# Step_Moter_Control.net
KiCad netlist of a schematic drawn in Altium Designer
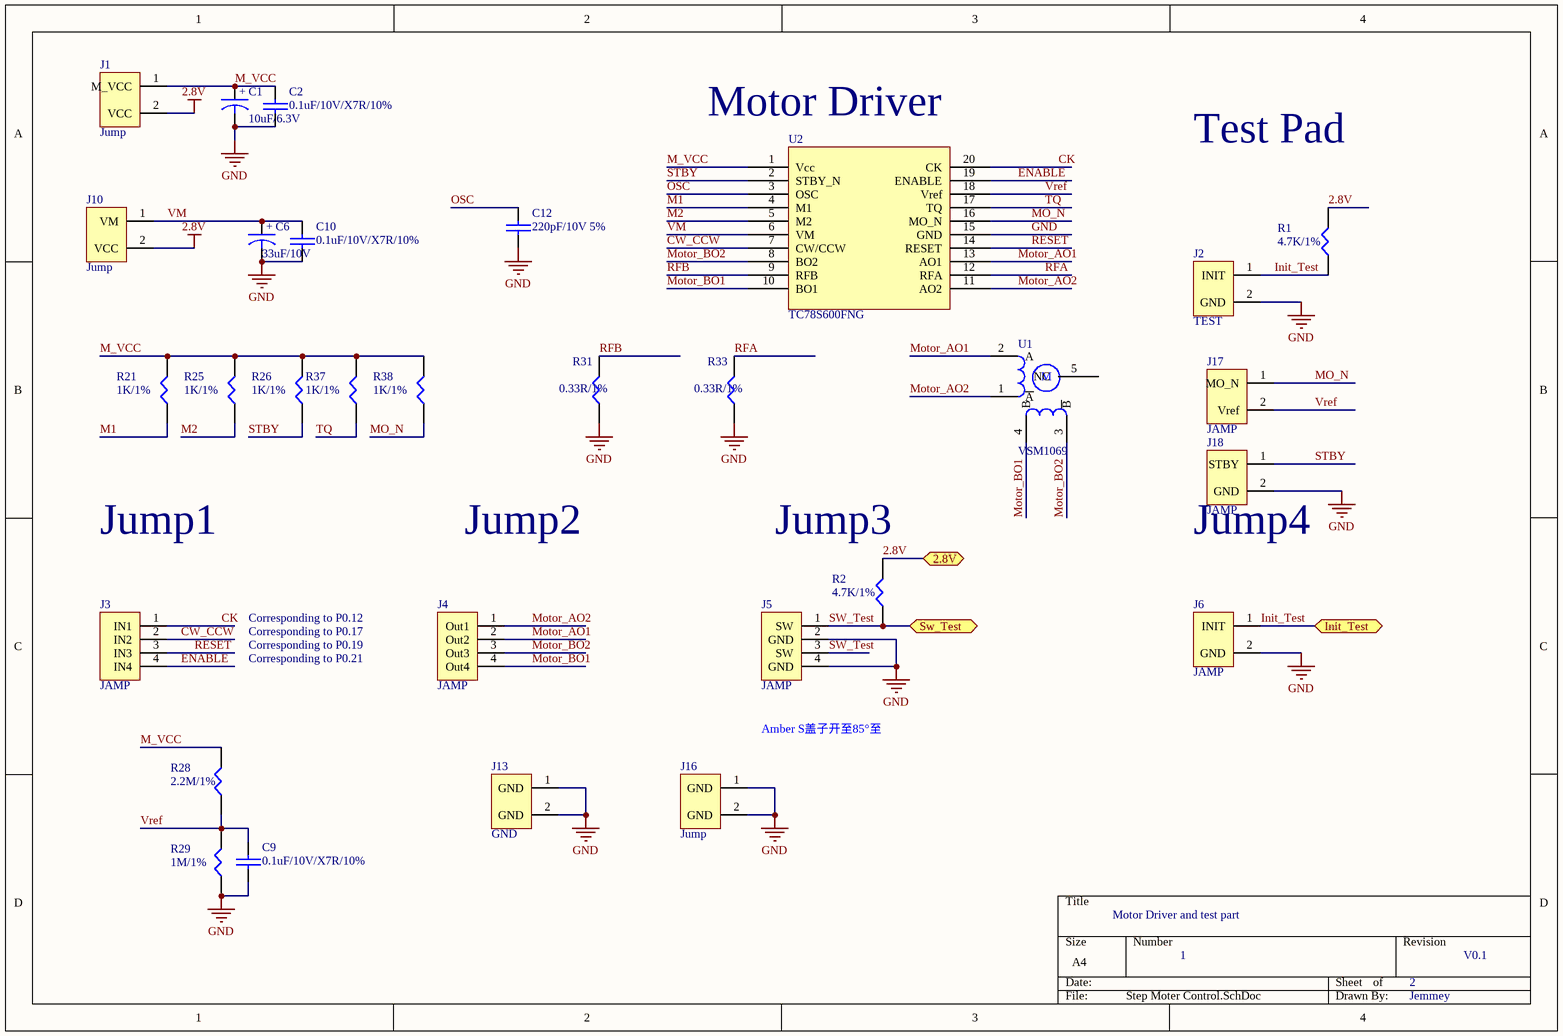
[diagram p0: Step Moter Control.SchDoc]

(export (version "E")
  (design (tool "Eeschema 10.0.6"))
  (components
    (comp (ref "C1")
      (value "10uF/6.3V")
      (footprint "3216")
      (description "厂家：ROHM，型号：")
      (libsource (lib "MoJi LIB") (part "Capacitor"))
    )
    (comp (ref "C2")
      (value "0.1uF/10V/X7R/10%")
      (footprint "0402C")
      (description "厂家：Murata，型号：GRM155R71A104KA01D")
      (libsource (lib "*") (part "CAP"))
    )
    (comp (ref "C6")
      (value "33uF/10V")
      (footprint "3216")
      (description "厂家：ROHM，型号：")
      (libsource (lib "MoJi LIB") (part "Capacitor"))
    )
    (comp (ref "C9")
      (value "0.1uF/10V/X7R/10%")
      (footprint "0402C")
      (description "厂家：Murata，型号：GRM155R71A104KA01D")
      (libsource (lib "*") (part "CAP"))
    )
    (comp (ref "C10")
      (value "0.1uF/10V/X7R/10%")
      (footprint "0402C")
      (description "厂家：Murata，型号：GRM155R71A104KA01D")
      (libsource (lib "*") (part "CAP"))
    )
    (comp (ref "C12")
      (value "220pF/10V 5%")
      (footprint "0402C")
      (description "厂家：Murata，型号：GRM155R71A104KA01D")
      (libsource (lib "*") (part "CAP"))
    )
    (comp (ref "J1")
      (value "Jump")
      (footprint "Debug- 1.27*2")
      (description "厂家：暂定，型号：暂定")
      (libsource (lib "") (part "JAMP_2"))
    )
    (comp (ref "J2")
      (value "TEST")
      (footprint "Debug- 1.27*2")
      (description "厂家：暂定，型号：暂定")
      (libsource (lib "Step Moter Control") (part "TEST"))
    )
    (comp (ref "J3")
      (value "JAMP")
      (footprint "Debug- 1.27*4")
      (description "厂家：暂定，型号：暂定")
      (libsource (lib "Step Moter Control") (part "JAMP"))
    )
    (comp (ref "J4")
      (value "JAMP")
      (footprint "Debug- 1.27*4")
      (description "厂家：暂定，型号：暂定")
      (libsource (lib "") (part "JAMP_1"))
    )
    (comp (ref "J5")
      (value "JAMP")
      (footprint "Debug- 1.27*4")
      (description "厂家：暂定，型号：暂定")
      (libsource (lib "") (part "JAMP_3"))
    )
    (comp (ref "J6")
      (value "JAMP")
      (footprint "Debug- 1.27*2")
      (description "厂家：暂定，型号：暂定")
      (libsource (lib "") (part "JAMP_2"))
    )
    (comp (ref "J10")
      (value "Jump")
      (footprint "Debug- 1.27*2")
      (description "厂家：暂定，型号：暂定")
      (libsource (lib "") (part "JAMP_2"))
    )
    (comp (ref "J13")
      (value "GND")
      (footprint "Debug- 1.27*2")
      (description "厂家：暂定，型号：暂定")
      (libsource (lib "") (part "JAMP_2"))
    )
    (comp (ref "J16")
      (value "Jump")
      (footprint "Debug- 1.27*2")
      (description "厂家：暂定，型号：暂定")
      (libsource (lib "") (part "JAMP_2"))
    )
    (comp (ref "J17")
      (value "JAMP")
      (footprint "Debug- 1.27*2")
      (description "厂家：暂定，型号：暂定")
      (libsource (lib "") (part "JAMP_2"))
    )
    (comp (ref "J18")
      (value "JAMP")
      (footprint "Debug- 1.27*2")
      (description "厂家：暂定，型号：暂定")
      (libsource (lib "") (part "JAMP_2"))
    )
    (comp (ref "R1")
      (value "4.7K/1%")
      (footprint "0402R")
      (description "厂家：Yageo，型号：RC0402FR-074K7L")
      (libsource (lib "*") (part "RES1"))
    )
    (comp (ref "R2")
      (value "4.7K/1%")
      (footprint "0402R")
      (description "厂家：Yageo，型号：RC0402FR-074K7L")
      (libsource (lib "*") (part "RES1"))
    )
    (comp (ref "R21")
      (value "1K/1%")
      (footprint "0402R")
      (description "厂家：Yageo，型号：RC0402FR-074K7L")
      (libsource (lib "*") (part "RES1"))
    )
    (comp (ref "R25")
      (value "1K/1%")
      (footprint "0402R")
      (description "厂家：Yageo，型号：RC0402FR-074K7L")
      (libsource (lib "*") (part "RES1"))
    )
    (comp (ref "R26")
      (value "1K/1%")
      (footprint "0402R")
      (description "厂家：Yageo，型号：RC0402FR-074K7L")
      (libsource (lib "*") (part "RES1"))
    )
    (comp (ref "R28")
      (value "2.2M/1%")
      (footprint "0402R")
      (description "厂家：Yageo，型号：RC0402FR-074K7L")
      (libsource (lib "*") (part "RES1"))
    )
    (comp (ref "R29")
      (value "1M/1%")
      (footprint "0402R")
      (description "厂家：Yageo，型号：RC0402FR-074K7L")
      (libsource (lib "*") (part "RES1"))
    )
    (comp (ref "R31")
      (value "0.33R/1%")
      (footprint "0603R")
      (description "厂家：Yageo，型号：RC0402FR-074K7L")
      (libsource (lib "*") (part "RES1"))
    )
    (comp (ref "R33")
      (value "0.33R/1%")
      (footprint "0603R")
      (description "厂家：Yageo，型号：RC0402FR-074K7L")
      (libsource (lib "*") (part "RES1"))
    )
    (comp (ref "R37")
      (value "1K/1%")
      (footprint "0402R")
      (description "厂家：Yageo，型号：RC0402FR-074K7L")
      (libsource (lib "*") (part "RES1"))
    )
    (comp (ref "R38")
      (value "1K/1%")
      (footprint "0402R")
      (description "厂家：Yageo，型号：RC0402FR-074K7L")
      (libsource (lib "*") (part "RES1"))
    )
    (comp (ref "U1")
      (value "VSM1069")
      (footprint "6200")
      (description "厂家：常州唯可泰，型号：VSM1069；二相步进电机")
      (libsource (lib "Step Moter Control") (part "VSM1069"))
    )
    (comp (ref "U2")
      (value "TC78S600FNG")
      (footprint "TSSOP-20")
      (libsource (lib "Step Moter Control") (part "TC78S600FNG"))
    )
  )
  (nets
    (net (code "1") (name "/CK") (class "Default")
      (node (ref "J3") (pin "1") (pinfunction "IN1_1") (pintype "passive"))
      (node (ref "U2") (pin "20") (pinfunction "CK_20") (pintype "passive"))
    )
    (net (code "2") (name "/CW_CCW") (class "Default")
      (node (ref "J3") (pin "2") (pinfunction "IN2_2") (pintype "passive"))
      (node (ref "U2") (pin "7") (pinfunction "CW/CCW_7") (pintype "passive"))
    )
    (net (code "3") (name "/ENABLE") (class "Default")
      (node (ref "J3") (pin "4") (pinfunction "IN4_4") (pintype "passive"))
      (node (ref "U2") (pin "19") (pinfunction "ENABLE_19") (pintype "passive"))
    )
    (net (code "4") (name "/Init_Test") (class "Default")
      (node (ref "J2") (pin "1") (pinfunction "INIT_1") (pintype "passive"))
      (node (ref "J6") (pin "1") (pinfunction "VM_1") (pintype "passive"))
      (node (ref "R1") (pin "1") (pinfunction "1_1") (pintype "passive"))
    )
    (net (code "5") (name "/M1") (class "Default")
      (node (ref "R21") (pin "1") (pinfunction "1_1") (pintype "passive"))
      (node (ref "U2") (pin "4") (pinfunction "M1_4") (pintype "passive"))
    )
    (net (code "6") (name "/M2") (class "Default")
      (node (ref "R25") (pin "1") (pinfunction "1_1") (pintype "passive"))
      (node (ref "U2") (pin "5") (pinfunction "M2_5") (pintype "passive"))
    )
    (net (code "7") (name "/MO_N") (class "Default")
      (node (ref "J17") (pin "1") (pinfunction "VM_1") (pintype "passive"))
      (node (ref "R38") (pin "1") (pinfunction "1_1") (pintype "passive"))
      (node (ref "U2") (pin "16") (pinfunction "MO_N_16") (pintype "passive"))
    )
    (net (code "8") (name "/M_VCC") (class "Default")
      (node (ref "C1") (pin "1") (pinfunction "1_1") (pintype "passive"))
      (node (ref "C2") (pin "1") (pinfunction "1_1") (pintype "passive"))
      (node (ref "J1") (pin "1") (pinfunction "VM_1") (pintype "passive"))
      (node (ref "R21") (pin "2") (pinfunction "2_2") (pintype "passive"))
      (node (ref "R25") (pin "2") (pinfunction "2_2") (pintype "passive"))
      (node (ref "R26") (pin "2") (pinfunction "2_2") (pintype "passive"))
      (node (ref "R28") (pin "2") (pinfunction "2_2") (pintype "passive"))
      (node (ref "R37") (pin "2") (pinfunction "2_2") (pintype "passive"))
      (node (ref "R38") (pin "2") (pinfunction "2_2") (pintype "passive"))
      (node (ref "U2") (pin "1") (pinfunction "Vcc_1") (pintype "passive"))
    )
    (net (code "9") (name "/Motor_AO1") (class "Default")
      (node (ref "J4") (pin "2") (pinfunction "Out2_2") (pintype "passive"))
      (node (ref "U1") (pin "2") (pinfunction "A_2") (pintype "passive"))
      (node (ref "U2") (pin "13") (pinfunction "AO1_13") (pintype "passive"))
    )
    (net (code "10") (name "/Motor_AO2") (class "Default")
      (node (ref "J4") (pin "1") (pinfunction "Out1_1") (pintype "passive"))
      (node (ref "U1") (pin "1") (pinfunction "~{A}_1") (pintype "passive"))
      (node (ref "U2") (pin "11") (pinfunction "AO2_11") (pintype "passive"))
    )
    (net (code "11") (name "/Motor_BO1") (class "Default")
      (node (ref "J4") (pin "4") (pinfunction "Out4_4") (pintype "passive"))
      (node (ref "U1") (pin "4") (pinfunction "B_4") (pintype "passive"))
      (node (ref "U2") (pin "10") (pinfunction "BO1_10") (pintype "passive"))
    )
    (net (code "12") (name "/Motor_BO2") (class "Default")
      (node (ref "J4") (pin "3") (pinfunction "Out3_3") (pintype "passive"))
      (node (ref "U1") (pin "3") (pinfunction "~{B}_3") (pintype "passive"))
      (node (ref "U2") (pin "8") (pinfunction "BO2_8") (pintype "passive"))
    )
    (net (code "13") (name "/OSC") (class "Default")
      (node (ref "C12") (pin "1") (pinfunction "1_1") (pintype "passive"))
      (node (ref "U2") (pin "3") (pinfunction "OSC_3") (pintype "passive"))
    )
    (net (code "14") (name "/RESET") (class "Default")
      (node (ref "J3") (pin "3") (pinfunction "IN3_3") (pintype "passive"))
      (node (ref "U2") (pin "14") (pinfunction "RESET_14") (pintype "passive"))
    )
    (net (code "15") (name "/RFA") (class "Default")
      (node (ref "R33") (pin "2") (pinfunction "2_2") (pintype "passive"))
      (node (ref "U2") (pin "12") (pinfunction "RFA_12") (pintype "passive"))
    )
    (net (code "16") (name "/RFB") (class "Default")
      (node (ref "R31") (pin "2") (pinfunction "2_2") (pintype "passive"))
      (node (ref "U2") (pin "9") (pinfunction "RFB_9") (pintype "passive"))
    )
    (net (code "17") (name "/STBY") (class "Default")
      (node (ref "J18") (pin "1") (pinfunction "VM_1") (pintype "passive"))
      (node (ref "R26") (pin "1") (pinfunction "1_1") (pintype "passive"))
      (node (ref "U2") (pin "2") (pinfunction "STBY_N_2") (pintype "passive"))
    )
    (net (code "18") (name "/SW_Test") (class "Default")
      (node (ref "J5") (pin "1") (pinfunction "SW_1") (pintype "passive"))
      (node (ref "J5") (pin "3") (pinfunction "SW_3") (pintype "passive"))
      (node (ref "R2") (pin "1") (pinfunction "1_1") (pintype "passive"))
    )
    (net (code "19") (name "/TQ") (class "Default")
      (node (ref "R37") (pin "1") (pinfunction "1_1") (pintype "passive"))
      (node (ref "U2") (pin "17") (pinfunction "TQ_17") (pintype "passive"))
    )
    (net (code "20") (name "/VM") (class "Default")
      (node (ref "C10") (pin "1") (pinfunction "1_1") (pintype "passive"))
      (node (ref "C6") (pin "1") (pinfunction "1_1") (pintype "passive"))
      (node (ref "J10") (pin "1") (pinfunction "VM_1") (pintype "passive"))
      (node (ref "U2") (pin "6") (pinfunction "VM_6") (pintype "passive"))
    )
    (net (code "21") (name "/Vref") (class "Default")
      (node (ref "C9") (pin "1") (pinfunction "1_1") (pintype "passive"))
      (node (ref "J17") (pin "2") (pinfunction "VCC_2") (pintype "passive"))
      (node (ref "R28") (pin "1") (pinfunction "1_1") (pintype "passive"))
      (node (ref "R29") (pin "2") (pinfunction "2_2") (pintype "passive"))
      (node (ref "U2") (pin "18") (pinfunction "Vref_18") (pintype "passive"))
    )
    (net (code "22") (name "2.8V") (class "Default")
      (node (ref "J1") (pin "2") (pinfunction "VCC_2") (pintype "passive"))
      (node (ref "J10") (pin "2") (pinfunction "VCC_2") (pintype "passive"))
      (node (ref "R1") (pin "2") (pinfunction "2_2") (pintype "passive"))
      (node (ref "R2") (pin "2") (pinfunction "2_2") (pintype "passive"))
    )
    (net (code "23") (name "GND") (class "Default")
      (node (ref "C1") (pin "2") (pinfunction "2_2") (pintype "passive"))
      (node (ref "C10") (pin "2") (pinfunction "2_2") (pintype "passive"))
      (node (ref "C12") (pin "2") (pinfunction "2_2") (pintype "passive"))
      (node (ref "C2") (pin "2") (pinfunction "2_2") (pintype "passive"))
      (node (ref "C6") (pin "2") (pinfunction "2_2") (pintype "passive"))
      (node (ref "C9") (pin "2") (pinfunction "2_2") (pintype "passive"))
      (node (ref "J13") (pin "1") (pinfunction "VM_1") (pintype "passive"))
      (node (ref "J13") (pin "2") (pinfunction "VCC_2") (pintype "passive"))
      (node (ref "J16") (pin "1") (pinfunction "VM_1") (pintype "passive"))
      (node (ref "J16") (pin "2") (pinfunction "VCC_2") (pintype "passive"))
      (node (ref "J18") (pin "2") (pinfunction "VCC_2") (pintype "passive"))
      (node (ref "J2") (pin "2") (pinfunction "GND_2") (pintype "passive"))
      (node (ref "J5") (pin "2") (pinfunction "GND_2") (pintype "passive"))
      (node (ref "J5") (pin "4") (pinfunction "GND_4") (pintype "passive"))
      (node (ref "J6") (pin "2") (pinfunction "VCC_2") (pintype "passive"))
      (node (ref "R29") (pin "1") (pinfunction "1_1") (pintype "passive"))
      (node (ref "R31") (pin "1") (pinfunction "1_1") (pintype "passive"))
      (node (ref "R33") (pin "1") (pinfunction "1_1") (pintype "passive"))
      (node (ref "U2") (pin "15") (pinfunction "GND_15") (pintype "passive"))
    )
    (net (code "24") (name "unconnected-(U1-NC-Pad5)") (class "Default")
      (node (ref "U1") (pin "5") (pinfunction "NC_5") (pintype "passive"))
    )
  )
)
